# fonte_5v_12v.net
KiCad netlist of a schematic drawn in EAGLE
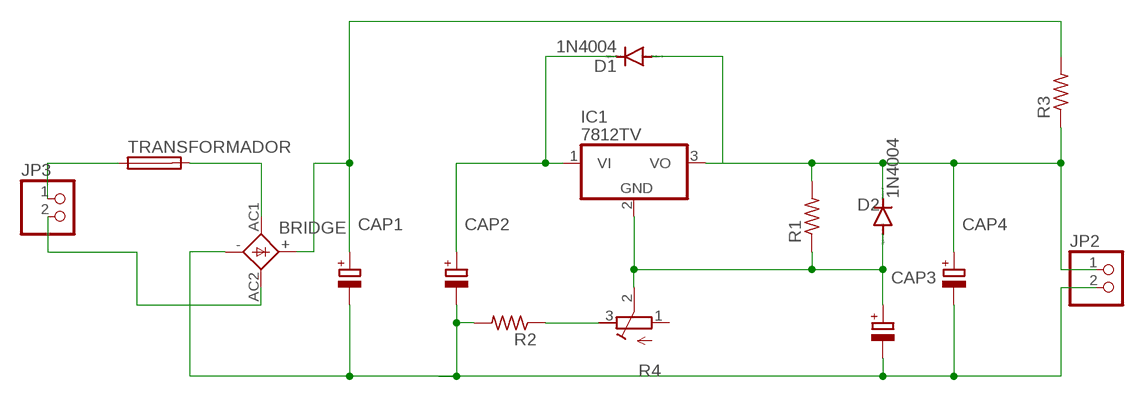
[diagram p0: schematic, sheet 1]

(export (version "E")
  (design (tool "Eeschema 10.0.6"))
  (components
    (comp (ref "BRIDGE")
      (value "2KBB-R")
      (footprint "eagle-import:2KBB-R")
      (libsource (lib "eagle-import") (part "2KBB-R"))
    )
    (comp (ref "CAP1")
      (value "CPOL-EUE5-13")
      (footprint "eagle-import:E5-13")
      (libsource (lib "eagle-import") (part "CPOL-EUE5-13"))
    )
    (comp (ref "CAP2")
      (value "CPOL-EUE5-13")
      (footprint "eagle-import:E5-13")
      (libsource (lib "eagle-import") (part "CPOL-EUE5-13"))
    )
    (comp (ref "CAP3")
      (value "CPOL-EUE5-13")
      (footprint "eagle-import:E5-13")
      (libsource (lib "eagle-import") (part "CPOL-EUE5-13"))
    )
    (comp (ref "CAP4")
      (value "CPOL-EUE5-13")
      (footprint "eagle-import:E5-13")
      (libsource (lib "eagle-import") (part "CPOL-EUE5-13"))
    )
    (comp (ref "D1")
      (value "1N4004")
      (footprint "eagle-import:DO41-10")
      (libsource (lib "eagle-import") (part "1N4004"))
    )
    (comp (ref "D2")
      (value "1N4004")
      (footprint "eagle-import:DO41-10")
      (libsource (lib "eagle-import") (part "1N4004"))
    )
    (comp (ref "IC1")
      (value "7812TV")
      (footprint "eagle-import:TO220V")
      (libsource (lib "eagle-import") (part "78TV12"))
    )
    (comp (ref "JP2")
      (value "PINHD-1X2")
      (footprint "eagle-import:1X02")
      (libsource (lib "eagle-import") (part "PINHD-1X2"))
    )
    (comp (ref "JP3")
      (value "PINHD-1X2")
      (footprint "eagle-import:1X02")
      (libsource (lib "eagle-import") (part "PINHD-1X2"))
    )
    (comp (ref "R1")
      (value "R-US_0204/7")
      (footprint "eagle-import:0204_7")
      (libsource (lib "eagle-import") (part "R-US_0204/7"))
    )
    (comp (ref "R2")
      (value "R-US_0204/7")
      (footprint "eagle-import:0204_7")
      (libsource (lib "eagle-import") (part "R-US_0204/7"))
    )
    (comp (ref "R3")
      (value "R-US_0204/7")
      (footprint "eagle-import:0204_7")
      (libsource (lib "eagle-import") (part "R-US_0204/7"))
    )
    (comp (ref "R4")
      (value "R-TRIMM3339P")
      (footprint "eagle-import:RTRIM3339P")
      (libsource (lib "eagle-import") (part "R-TRIMM3339P"))
    )
    (comp (ref "TRANSFORMADOR")
      (value "SH22,5")
      (footprint "eagle-import:SH22,5")
      (fields (field (name "MF") "SCHURTER") (field (name "MPN") "0031.8201"))
      (libsource (lib "eagle-import") (part "SH22,5"))
    )
  )
  (nets
    (net (code "1") (name "Net-(BRIDGE-Pad+)") (class "Default")
      (node (ref "BRIDGE") (pin "+") (pinfunction "+_+") (pintype "passive"))
      (node (ref "CAP1") (pin "+") (pinfunction "+_+") (pintype "passive"))
      (node (ref "R3") (pin "2") (pinfunction "2_2") (pintype "passive"))
    )
    (net (code "2") (name "Net-(BRIDGE-Pad-)") (class "Default")
      (node (ref "BRIDGE") (pin "-") (pinfunction "-_-") (pintype "passive"))
      (node (ref "CAP1") (pin "-") (pinfunction "-_-") (pintype "passive"))
      (node (ref "CAP2") (pin "-") (pinfunction "-_-") (pintype "passive"))
      (node (ref "CAP3") (pin "-") (pinfunction "-_-") (pintype "passive"))
      (node (ref "CAP4") (pin "-") (pinfunction "-_-") (pintype "passive"))
      (node (ref "JP2") (pin "2") (pinfunction "2_2") (pintype "passive"))
      (node (ref "R2") (pin "2") (pinfunction "2_2") (pintype "passive"))
    )
    (net (code "3") (name "Net-(BRIDGE-PadAC1)") (class "Default")
      (node (ref "BRIDGE") (pin "AC1") (pinfunction "AC1_AC1") (pintype "passive"))
      (node (ref "TRANSFORMADOR") (pin "2") (pinfunction "2_2") (pintype "passive"))
    )
    (net (code "4") (name "Net-(BRIDGE-PadAC2)") (class "Default")
      (node (ref "BRIDGE") (pin "AC2") (pinfunction "AC2_AC2") (pintype "passive"))
      (node (ref "JP3") (pin "2") (pinfunction "2_2") (pintype "passive"))
    )
    (net (code "5") (name "Net-(IC1-GND)") (class "Default")
      (node (ref "CAP3") (pin "+") (pinfunction "+_+") (pintype "passive"))
      (node (ref "D2") (pin "A") (pinfunction "A_A") (pintype "passive"))
      (node (ref "IC1") (pin "2") (pinfunction "GND_2") (pintype "passive"))
      (node (ref "R1") (pin "1") (pinfunction "1_1") (pintype "passive"))
      (node (ref "R4") (pin "2") (pinfunction "S_2") (pintype "passive"))
    )
    (net (code "6") (name "Net-(IC1-VI)") (class "Default")
      (node (ref "CAP2") (pin "+") (pinfunction "+_+") (pintype "passive"))
      (node (ref "D1") (pin "C") (pinfunction "C_C") (pintype "passive"))
      (node (ref "IC1") (pin "1") (pinfunction "VI_1") (pintype "input"))
    )
    (net (code "7") (name "Net-(IC1-VO)") (class "Default")
      (node (ref "CAP4") (pin "+") (pinfunction "+_+") (pintype "passive"))
      (node (ref "D1") (pin "A") (pinfunction "A_A") (pintype "passive"))
      (node (ref "D2") (pin "C") (pinfunction "C_C") (pintype "passive"))
      (node (ref "IC1") (pin "3") (pinfunction "VO_3") (pintype "passive"))
      (node (ref "JP2") (pin "1") (pinfunction "1_1") (pintype "passive"))
      (node (ref "R1") (pin "2") (pinfunction "2_2") (pintype "passive"))
      (node (ref "R3") (pin "1") (pinfunction "1_1") (pintype "passive"))
    )
    (net (code "8") (name "Net-(JP3-Pad1)") (class "Default")
      (node (ref "JP3") (pin "1") (pinfunction "1_1") (pintype "passive"))
      (node (ref "TRANSFORMADOR") (pin "1") (pinfunction "1_1") (pintype "passive"))
    )
    (net (code "9") (name "Net-(R4-E)") (class "Default")
      (node (ref "R2") (pin "1") (pinfunction "1_1") (pintype "passive"))
      (node (ref "R4") (pin "3") (pinfunction "E_3") (pintype "passive"))
    )
    (net (code "10") (name "unconnected-(R4-A-Pad1)") (class "Default")
      (node (ref "R4") (pin "1") (pinfunction "A_1") (pintype "passive"))
    )
  )
)
